# SCH_NFC-Card-Yuyang_2024-10-09.net
KiCad netlist of a schematic drawn in EasyEDA
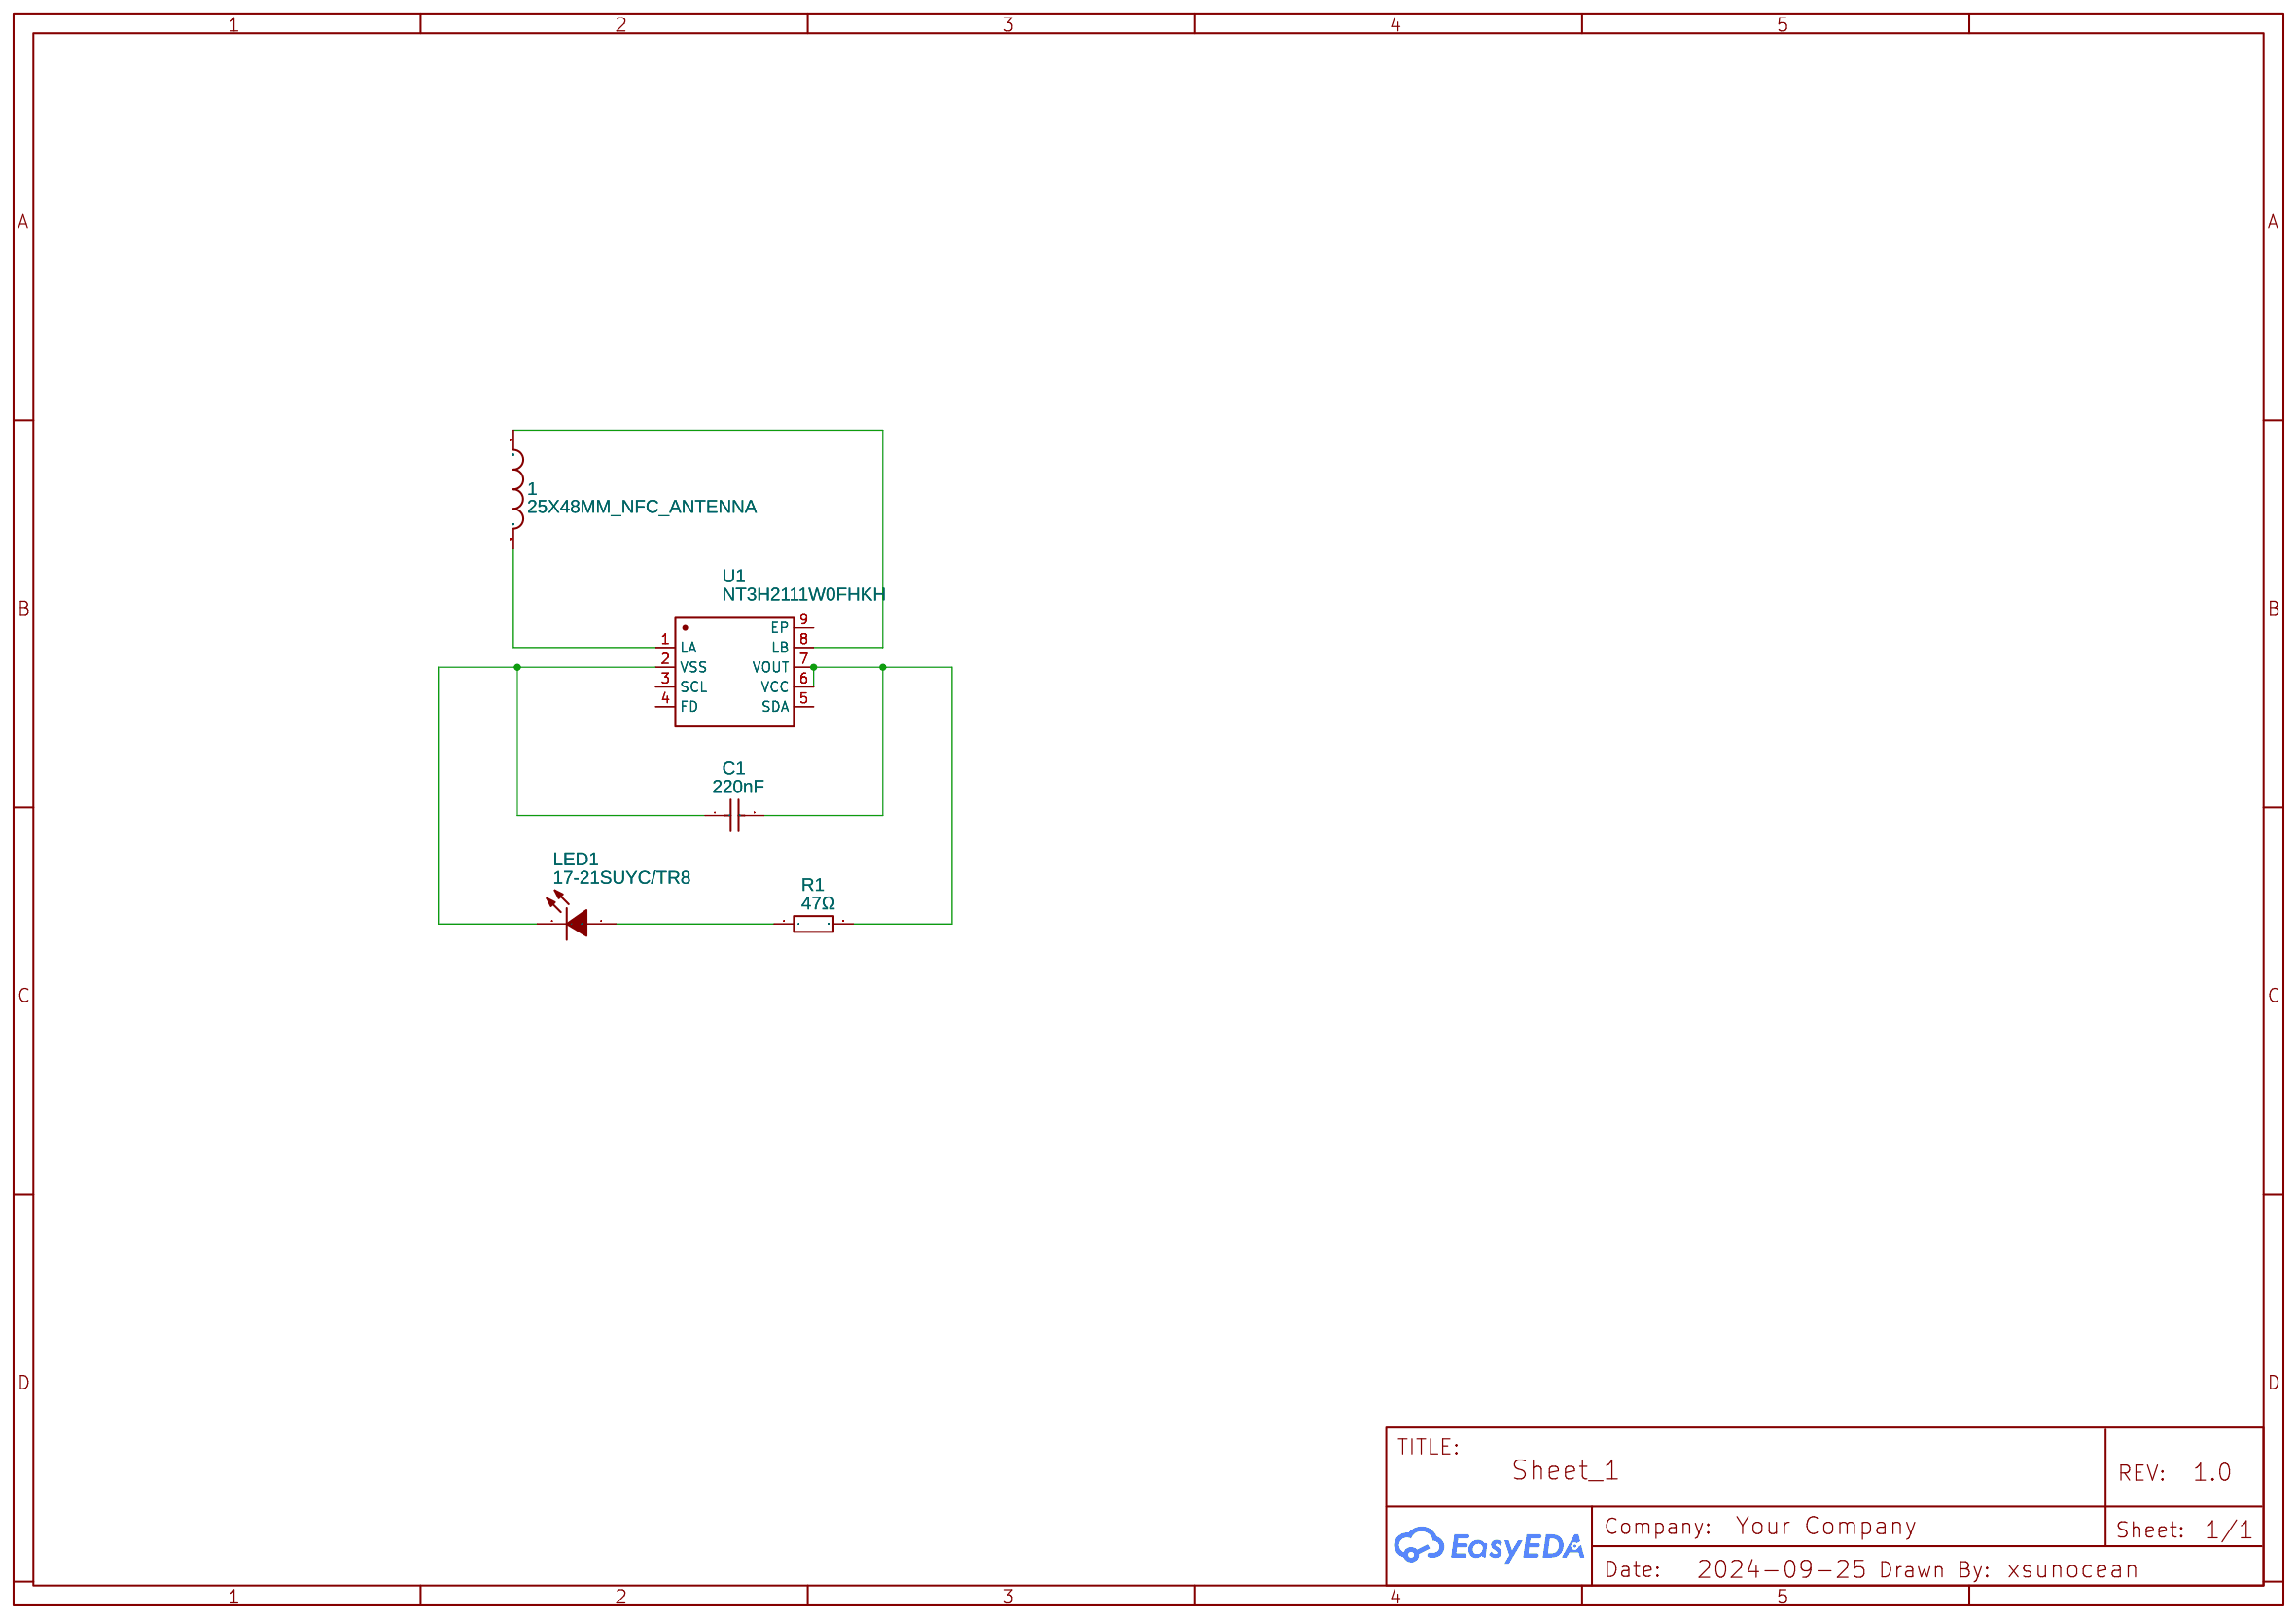
[diagram p0: schematic sheet]

(export (version "E")
  (design (tool "Eeschema 10.0.6"))
  (components
    (comp (ref "1") (value "25X48MM_NFC_ANTENNA") (libsource (lib "") (part "25X48MM_NFC_ANTENNA")))
    (comp (ref "C1")
      (value "220nF")
      (fields
        (field (name "Manufacturer Part") "CL10B224KA8NNNC")
        (field (name "Manufacturer") "SAMSUNG(三星)")
      )
      (libsource (lib "") (part "CL10B224KA8NNNC"))
    )
    (comp (ref "LED1")
      (value "17-21SUYC/TR8")
      (fields (field (name "Manufacturer Part") "KT-0805黄灯") (field (name "Manufacturer") "KENTO"))
      (libsource (lib "") (part "17-21SUYC/TR8"))
    )
    (comp (ref "R1")
      (value "47Ω")
      (fields
        (field (name "Manufacturer Part") "0603WAF470JT5E")
        (field (name "Manufacturer") "UNI-ROYAL(厚声)")
      )
      (libsource (lib "") (part "0603WAF470JT5E"))
    )
    (comp (ref "U1")
      (value "NT3H2111W0FHKH")
      (fields (field (name "Manufacturer") "NXP(恩智浦)"))
      (libsource (lib "") (part "NT3H2111W0FHKH"))
    )
  )
  (nets
    (net (code "1") (name "Net-(LED1-+)") (class "Default")
      (node (ref "LED1") (pin "1") (pinfunction "+_1") (pintype "unspecified"))
      (node (ref "R1") (pin "1") (pinfunction "1_1") (pintype "input"))
    )
    (net (code "2") (name "Net-(LED1--)") (class "Default")
      (node (ref "C1") (pin "1") (pinfunction "1_1") (pintype "input"))
      (node (ref "LED1") (pin "2") (pinfunction "-_2") (pintype "unspecified"))
      (node (ref "U1") (pin "2") (pinfunction "VSS_2") (pintype "unspecified"))
    )
    (net (code "3") (name "Net-(U1-LA)") (class "Default")
      (node (ref "1") (pin "P$2") (pinfunction "P$2_P$2") (pintype "bidirectional"))
      (node (ref "U1") (pin "1") (pinfunction "LA_1") (pintype "unspecified"))
    )
    (net (code "4") (name "Net-(U1-LB)") (class "Default")
      (node (ref "1") (pin "P$1") (pinfunction "P$1_P$1") (pintype "bidirectional"))
      (node (ref "U1") (pin "8") (pinfunction "LB_8") (pintype "unspecified"))
    )
    (net (code "5") (name "Net-(U1-VCC)") (class "Default")
      (node (ref "C1") (pin "2") (pinfunction "2_2") (pintype "input"))
      (node (ref "R1") (pin "2") (pinfunction "2_2") (pintype "input"))
      (node (ref "U1") (pin "6") (pinfunction "VCC_6") (pintype "unspecified"))
      (node (ref "U1") (pin "7") (pinfunction "VOUT_7") (pintype "unspecified"))
    )
    (net (code "6") (name "unconnected-(U1-EP-Pad9)") (class "Default")
      (node (ref "U1") (pin "9") (pinfunction "EP_9") (pintype "unspecified"))
    )
    (net (code "7") (name "unconnected-(U1-FD-Pad4)") (class "Default")
      (node (ref "U1") (pin "4") (pinfunction "FD_4") (pintype "unspecified"))
    )
    (net (code "8") (name "unconnected-(U1-SCL-Pad3)") (class "Default")
      (node (ref "U1") (pin "3") (pinfunction "SCL_3") (pintype "unspecified"))
    )
    (net (code "9") (name "unconnected-(U1-SDA-Pad5)") (class "Default")
      (node (ref "U1") (pin "5") (pinfunction "SDA_5") (pintype "unspecified"))
    )
  )
)
